# control.net
KiCad netlist of a schematic drawn in Altium Designer
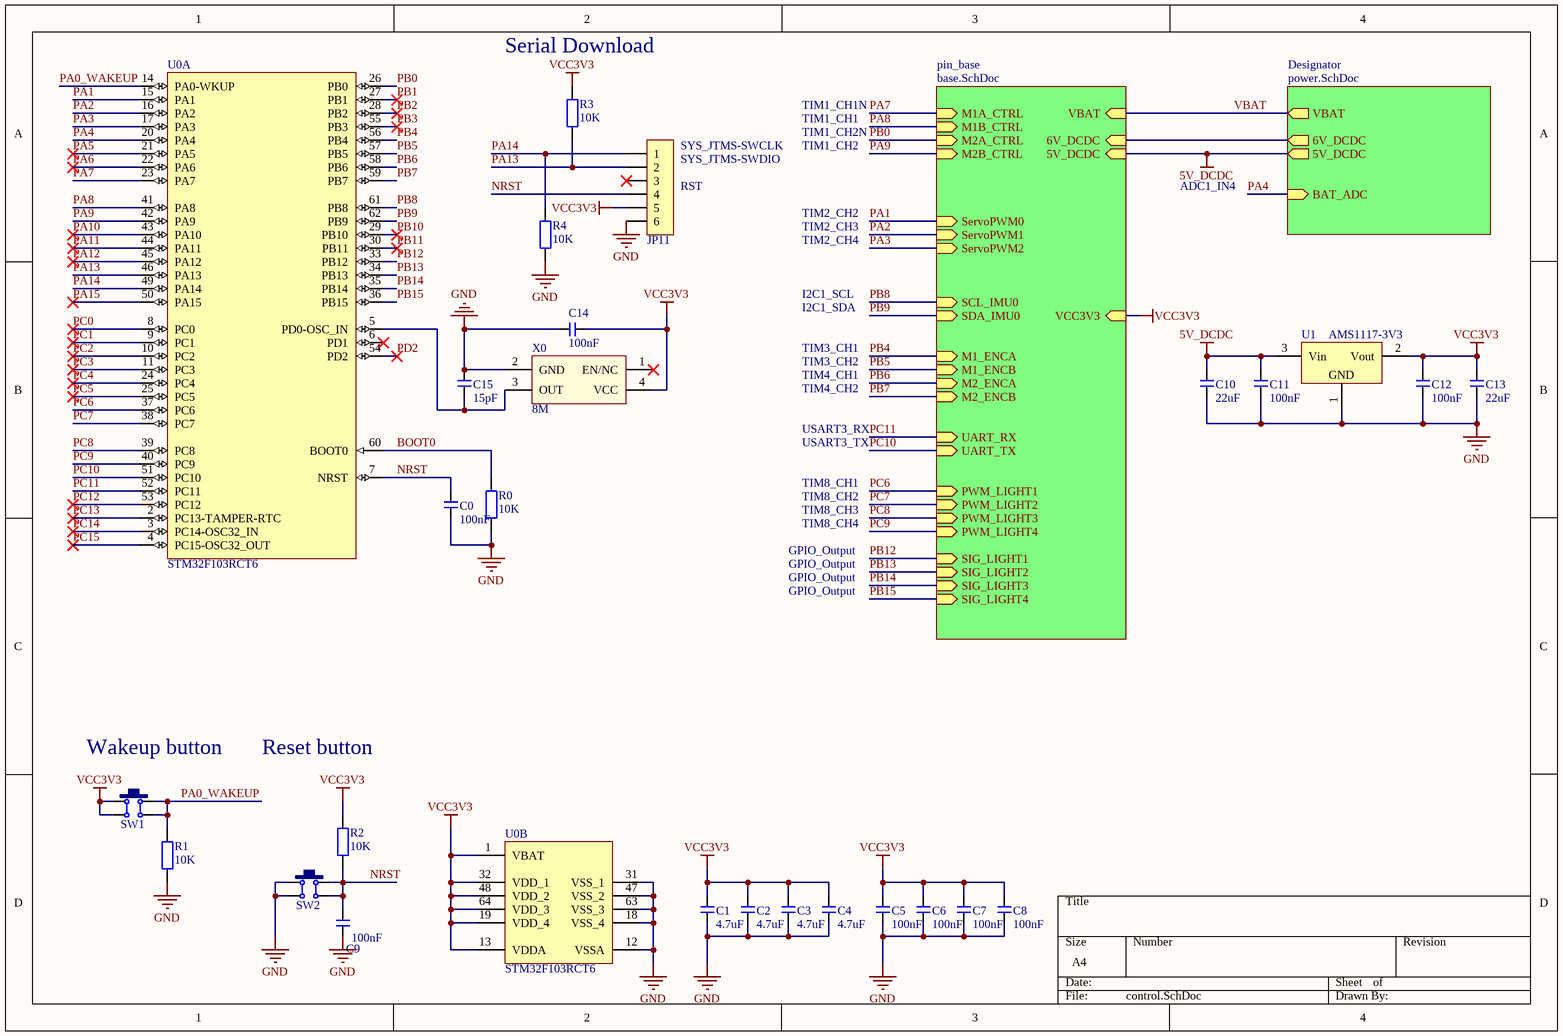
[diagram p0: control.SchDoc]

(export (version "E")
  (design (tool "Eeschema 10.0.6"))
  (components
    (comp (ref "C0")
      (value "100nF")
      (footprint "C 0402_M")
      (description "贴片电容")
      (libsource (lib "RLC") (part "C"))
    )
    (comp (ref "C1")
      (value "4.7uF")
      (footprint "C 0603_M")
      (description "贴片电容")
      (libsource (lib "RLC") (part "C"))
    )
    (comp (ref "C2")
      (value "4.7uF")
      (footprint "C 0603_M")
      (description "贴片电容")
      (libsource (lib "RLC") (part "C"))
    )
    (comp (ref "C3")
      (value "4.7uF")
      (footprint "C 0603_M")
      (description "贴片电容")
      (libsource (lib "RLC") (part "C"))
    )
    (comp (ref "C4")
      (value "4.7uF")
      (footprint "C 0603_M")
      (description "贴片电容")
      (libsource (lib "RLC") (part "C"))
    )
    (comp (ref "C5")
      (value "100nF")
      (footprint "C 0402_M")
      (description "贴片电容")
      (libsource (lib "RLC") (part "C"))
    )
    (comp (ref "C6")
      (value "100nF")
      (footprint "C 0402_M")
      (description "贴片电容")
      (libsource (lib "RLC") (part "C"))
    )
    (comp (ref "C7")
      (value "100nF")
      (footprint "C 0402_M")
      (description "贴片电容")
      (libsource (lib "RLC") (part "C"))
    )
    (comp (ref "C8")
      (value "100nF")
      (footprint "C 0402_M")
      (description "贴片电容")
      (libsource (lib "RLC") (part "C"))
    )
    (comp (ref "C9")
      (value "100nF")
      (footprint "C 0402_M")
      (description "贴片电容")
      (libsource (lib "RLC") (part "C"))
    )
    (comp (ref "C10")
      (value "22uF")
      (footprint "C 1206_M")
      (description "贴片电容")
      (libsource (lib "RLC") (part "C"))
    )
    (comp (ref "C11")
      (value "100nF")
      (footprint "C 0402_M")
      (description "贴片电容")
      (libsource (lib "RLC") (part "C"))
    )
    (comp (ref "C12")
      (value "100nF")
      (footprint "C 0402_M")
      (description "贴片电容")
      (libsource (lib "RLC") (part "C"))
    )
    (comp (ref "C13")
      (value "22uF")
      (footprint "C 1206_M")
      (description "贴片电容")
      (libsource (lib "RLC") (part "C"))
    )
    (comp (ref "C14")
      (value "100nF")
      (footprint "C 0402_M")
      (description "贴片电容")
      (libsource (lib "RLC") (part "C"))
    )
    (comp (ref "C15")
      (value "15pF")
      (footprint "C 0402_M")
      (description "贴片电容")
      (libsource (lib "RLC") (part "C"))
    )
    (comp (ref "JP11")
      (value "HDR-1X6")
      (footprint "HDR2.54-WI-6P")
      (description "6P接插件")
      (fields (field (name "版权归属") "封装库来自淘宝 ID：黄晶宝石"))
      (libsource (lib "header") (part "Header 6"))
    )
    (comp (ref "R0")
      (value "10K")
      (footprint "R 0402_M")
      (description "贴片电阻")
      (libsource (lib "RLC") (part "R"))
    )
    (comp (ref "R1")
      (value "10K")
      (footprint "R 0402_M")
      (description "贴片电阻")
      (libsource (lib "RLC") (part "R"))
    )
    (comp (ref "R2")
      (value "10K")
      (footprint "R 0402_M")
      (description "贴片电阻")
      (libsource (lib "RLC") (part "R"))
    )
    (comp (ref "R3")
      (value "10K")
      (footprint "R 0402_M")
      (description "贴片电阻")
      (libsource (lib "RLC") (part "R"))
    )
    (comp (ref "R4")
      (value "10K")
      (footprint "R 0402_M")
      (description "贴片电阻")
      (libsource (lib "RLC") (part "R"))
    )
    (comp (ref "SW1")
      (value "6x6x5")
      (footprint "TSW SMD-6*6*4.3")
      (description "贴片6x6轻触开关")
      (libsource (lib "Schlib") (part "TSW SMD-6x6"))
    )
    (comp (ref "SW2")
      (value "6x6x5")
      (footprint "TSW SMD-6*6*4.3")
      (description "贴片6x6轻触开关")
      (libsource (lib "Schlib") (part "TSW SMD-6x6"))
    )
    (comp (ref "U0")
      (value "STM32F103RCT6")
      (footprint "LQFP64_M")
      (libsource (lib "Schlib") (part "STM32F103RCT6"))
    )
    (comp (ref "U1")
      (value "AMS1117-3V3")
      (footprint "SOT223_L")
      (description "三端稳压芯片")
      (libsource (lib "Schlib") (part "AMS1117"))
    )
    (comp (ref "X0")
      (value "8M")
      (footprint "OSC 3225-4P")
      (description "4脚有源晶振")
      (libsource (lib "Schlib") (part "XTAL-ACT-4P"))
    )
  )
  (nets
    (net (code "2") (name "/BOOT0") (class "Default")
      (node (ref "R0") (pin "2") (pinfunction "2_2") (pintype "passive"))
      (node (ref "U0") (pin "60") (pinfunction "BOOT0_60") (pintype "input"))
    )
    (net (code "3") (name "/NRST") (class "Default")
      (node (ref "C0") (pin "2") (pinfunction "2_2") (pintype "passive"))
      (node (ref "C9") (pin "2") (pinfunction "2_2") (pintype "passive"))
      (node (ref "JP11") (pin "4") (pinfunction "4_4") (pintype "passive"))
      (node (ref "R2") (pin "1") (pinfunction "1_1") (pintype "passive"))
      (node (ref "SW2") (pin "2") (pinfunction "2_2") (pintype "passive"))
      (node (ref "SW2") (pin "3") (pinfunction "3_3") (pintype "passive"))
      (node (ref "U0") (pin "7") (pinfunction "NRST_7") (pintype "bidirectional"))
    )
    (net (code "4") (name "/PA0_WAKEUP") (class "Default")
      (node (ref "R1") (pin "2") (pinfunction "2_2") (pintype "passive"))
      (node (ref "SW1") (pin "2") (pinfunction "2_2") (pintype "passive"))
      (node (ref "SW1") (pin "3") (pinfunction "3_3") (pintype "passive"))
      (node (ref "U0") (pin "14") (pinfunction "PA0-WKUP_14") (pintype "bidirectional"))
    )
    (net (code "5") (name "/PA1") (class "Default")
      (node (ref "U0") (pin "15") (pinfunction "PA1_15") (pintype "bidirectional"))
    )
    (net (code "6") (name "/PA2") (class "Default")
      (node (ref "U0") (pin "16") (pinfunction "PA2_16") (pintype "bidirectional"))
    )
    (net (code "7") (name "/PA3") (class "Default")
      (node (ref "U0") (pin "17") (pinfunction "PA3_17") (pintype "bidirectional"))
    )
    (net (code "8") (name "/PA4") (class "Default")
      (node (ref "U0") (pin "20") (pinfunction "PA4_20") (pintype "bidirectional"))
    )
    (net (code "9") (name "/PA5") (class "Default")
      (node (ref "U0") (pin "21") (pinfunction "PA5_21") (pintype "bidirectional+no_connect"))
    )
    (net (code "10") (name "/PA6") (class "Default")
      (node (ref "U0") (pin "22") (pinfunction "PA6_22") (pintype "bidirectional+no_connect"))
    )
    (net (code "11") (name "/PA7") (class "Default")
      (node (ref "U0") (pin "23") (pinfunction "PA7_23") (pintype "bidirectional"))
    )
    (net (code "12") (name "/PA8") (class "Default")
      (node (ref "U0") (pin "41") (pinfunction "PA8_41") (pintype "bidirectional"))
    )
    (net (code "13") (name "/PA9") (class "Default")
      (node (ref "U0") (pin "42") (pinfunction "PA9_42") (pintype "bidirectional"))
    )
    (net (code "14") (name "/PA10") (class "Default")
      (node (ref "U0") (pin "43") (pinfunction "PA10_43") (pintype "bidirectional+no_connect"))
    )
    (net (code "15") (name "/PA11") (class "Default")
      (node (ref "U0") (pin "44") (pinfunction "PA11_44") (pintype "bidirectional+no_connect"))
    )
    (net (code "16") (name "/PA12") (class "Default")
      (node (ref "U0") (pin "45") (pinfunction "PA12_45") (pintype "bidirectional+no_connect"))
    )
    (net (code "17") (name "/PA13") (class "Default")
      (node (ref "JP11") (pin "2") (pinfunction "2_2") (pintype "passive"))
      (node (ref "R3") (pin "1") (pinfunction "1_1") (pintype "passive"))
      (node (ref "U0") (pin "46") (pinfunction "PA13_46") (pintype "bidirectional"))
    )
    (net (code "18") (name "/PA14") (class "Default")
      (node (ref "JP11") (pin "1") (pinfunction "1_1") (pintype "passive"))
      (node (ref "R4") (pin "2") (pinfunction "2_2") (pintype "passive"))
      (node (ref "U0") (pin "49") (pinfunction "PA14_49") (pintype "bidirectional"))
    )
    (net (code "19") (name "/PA15") (class "Default")
      (node (ref "U0") (pin "50") (pinfunction "PA15_50") (pintype "bidirectional+no_connect"))
    )
    (net (code "20") (name "/PB0") (class "Default")
      (node (ref "U0") (pin "26") (pinfunction "PB0_26") (pintype "bidirectional"))
    )
    (net (code "21") (name "/PB1") (class "Default")
      (node (ref "U0") (pin "27") (pinfunction "PB1_27") (pintype "bidirectional+no_connect"))
    )
    (net (code "22") (name "/PB2") (class "Default")
      (node (ref "U0") (pin "28") (pinfunction "PB2_28") (pintype "bidirectional+no_connect"))
    )
    (net (code "23") (name "/PB3") (class "Default")
      (node (ref "U0") (pin "55") (pinfunction "PB3_55") (pintype "bidirectional+no_connect"))
    )
    (net (code "24") (name "/PB4") (class "Default")
      (node (ref "U0") (pin "56") (pinfunction "PB4_56") (pintype "bidirectional"))
    )
    (net (code "25") (name "/PB5") (class "Default")
      (node (ref "U0") (pin "57") (pinfunction "PB5_57") (pintype "bidirectional"))
    )
    (net (code "26") (name "/PB6") (class "Default")
      (node (ref "U0") (pin "58") (pinfunction "PB6_58") (pintype "bidirectional"))
    )
    (net (code "27") (name "/PB7") (class "Default")
      (node (ref "U0") (pin "59") (pinfunction "PB7_59") (pintype "bidirectional"))
    )
    (net (code "28") (name "/PB8") (class "Default")
      (node (ref "U0") (pin "61") (pinfunction "PB8_61") (pintype "bidirectional"))
    )
    (net (code "29") (name "/PB9") (class "Default")
      (node (ref "U0") (pin "62") (pinfunction "PB9_62") (pintype "bidirectional"))
    )
    (net (code "30") (name "/PB10") (class "Default")
      (node (ref "U0") (pin "29") (pinfunction "PB10_29") (pintype "bidirectional+no_connect"))
    )
    (net (code "31") (name "/PB11") (class "Default")
      (node (ref "U0") (pin "30") (pinfunction "PB11_30") (pintype "bidirectional+no_connect"))
    )
    (net (code "32") (name "/PB12") (class "Default")
      (node (ref "U0") (pin "33") (pinfunction "PB12_33") (pintype "bidirectional"))
    )
    (net (code "33") (name "/PB13") (class "Default")
      (node (ref "U0") (pin "34") (pinfunction "PB13_34") (pintype "bidirectional"))
    )
    (net (code "34") (name "/PB14") (class "Default")
      (node (ref "U0") (pin "35") (pinfunction "PB14_35") (pintype "bidirectional"))
    )
    (net (code "35") (name "/PB15") (class "Default")
      (node (ref "U0") (pin "36") (pinfunction "PB15_36") (pintype "bidirectional"))
    )
    (net (code "36") (name "/PC0") (class "Default")
      (node (ref "U0") (pin "8") (pinfunction "PC0_8") (pintype "bidirectional+no_connect"))
    )
    (net (code "37") (name "/PC1") (class "Default")
      (node (ref "U0") (pin "9") (pinfunction "PC1_9") (pintype "bidirectional+no_connect"))
    )
    (net (code "38") (name "/PC2") (class "Default")
      (node (ref "U0") (pin "10") (pinfunction "PC2_10") (pintype "bidirectional+no_connect"))
    )
    (net (code "39") (name "/PC3") (class "Default")
      (node (ref "U0") (pin "11") (pinfunction "PC3_11") (pintype "bidirectional+no_connect"))
    )
    (net (code "40") (name "/PC4") (class "Default")
      (node (ref "U0") (pin "24") (pinfunction "PC4_24") (pintype "bidirectional+no_connect"))
    )
    (net (code "41") (name "/PC5") (class "Default")
      (node (ref "U0") (pin "25") (pinfunction "PC5_25") (pintype "bidirectional+no_connect"))
    )
    (net (code "42") (name "/PC6") (class "Default")
      (node (ref "U0") (pin "37") (pinfunction "PC6_37") (pintype "bidirectional"))
    )
    (net (code "43") (name "/PC7") (class "Default")
      (node (ref "U0") (pin "38") (pinfunction "PC7_38") (pintype "bidirectional"))
    )
    (net (code "44") (name "/PC8") (class "Default")
      (node (ref "U0") (pin "39") (pinfunction "PC8_39") (pintype "bidirectional"))
    )
    (net (code "45") (name "/PC9") (class "Default")
      (node (ref "U0") (pin "40") (pinfunction "PC9_40") (pintype "bidirectional"))
    )
    (net (code "46") (name "/PC10") (class "Default")
      (node (ref "U0") (pin "51") (pinfunction "PC10_51") (pintype "bidirectional"))
    )
    (net (code "47") (name "/PC11") (class "Default")
      (node (ref "U0") (pin "52") (pinfunction "PC11_52") (pintype "bidirectional"))
    )
    (net (code "48") (name "/PC12") (class "Default")
      (node (ref "U0") (pin "53") (pinfunction "PC12_53") (pintype "bidirectional+no_connect"))
    )
    (net (code "49") (name "/PC13") (class "Default")
      (node (ref "U0") (pin "2") (pinfunction "PC13-TAMPER-RTC_2") (pintype "bidirectional+no_connect"))
    )
    (net (code "50") (name "/PC14") (class "Default")
      (node (ref "U0") (pin "3") (pinfunction "PC14-OSC32_IN_3") (pintype "bidirectional+no_connect"))
    )
    (net (code "51") (name "/PC15") (class "Default")
      (node (ref "U0") (pin "4") (pinfunction "PC15-OSC32_OUT_4") (pintype "bidirectional+no_connect"))
    )
    (net (code "52") (name "/PD2") (class "Default")
      (node (ref "U0") (pin "54") (pinfunction "PD2_54") (pintype "bidirectional+no_connect"))
    )
    (net (code "54") (name "5V_DCDC") (class "Default")
      (node (ref "C10") (pin "2") (pinfunction "2_2") (pintype "passive"))
      (node (ref "C11") (pin "2") (pinfunction "2_2") (pintype "passive"))
      (node (ref "U1") (pin "3") (pinfunction "Vin_3") (pintype "passive"))
    )
    (net (code "55") (name "GND") (class "Default")
      (node (ref "C0") (pin "1") (pinfunction "1_1") (pintype "passive"))
      (node (ref "C1") (pin "1") (pinfunction "1_1") (pintype "passive"))
      (node (ref "C10") (pin "1") (pinfunction "1_1") (pintype "passive"))
      (node (ref "C11") (pin "1") (pinfunction "1_1") (pintype "passive"))
      (node (ref "C12") (pin "1") (pinfunction "1_1") (pintype "passive"))
      (node (ref "C13") (pin "1") (pinfunction "1_1") (pintype "passive"))
      (node (ref "C14") (pin "2") (pinfunction "2_2") (pintype "passive"))
      (node (ref "C15") (pin "1") (pinfunction "1_1") (pintype "passive"))
      (node (ref "C2") (pin "1") (pinfunction "1_1") (pintype "passive"))
      (node (ref "C3") (pin "1") (pinfunction "1_1") (pintype "passive"))
      (node (ref "C4") (pin "1") (pinfunction "1_1") (pintype "passive"))
      (node (ref "C5") (pin "1") (pinfunction "1_1") (pintype "passive"))
      (node (ref "C6") (pin "1") (pinfunction "1_1") (pintype "passive"))
      (node (ref "C7") (pin "1") (pinfunction "1_1") (pintype "passive"))
      (node (ref "C8") (pin "1") (pinfunction "1_1") (pintype "passive"))
      (node (ref "C9") (pin "1") (pinfunction "1_1") (pintype "passive"))
      (node (ref "JP11") (pin "6") (pinfunction "6_6") (pintype "passive"))
      (node (ref "R0") (pin "1") (pinfunction "1_1") (pintype "passive"))
      (node (ref "R1") (pin "1") (pinfunction "1_1") (pintype "passive"))
      (node (ref "R4") (pin "1") (pinfunction "1_1") (pintype "passive"))
      (node (ref "SW2") (pin "1") (pinfunction "1_1") (pintype "passive"))
      (node (ref "SW2") (pin "4") (pinfunction "4_4") (pintype "passive"))
      (node (ref "U0") (pin "12") (pinfunction "VSSA_12") (pintype "power_in"))
      (node (ref "U0") (pin "18") (pinfunction "VSS_4_18") (pintype "power_in"))
      (node (ref "U0") (pin "31") (pinfunction "VSS_1_31") (pintype "power_in"))
      (node (ref "U0") (pin "47") (pinfunction "VSS_2_47") (pintype "power_in"))
      (node (ref "U0") (pin "63") (pinfunction "VSS_3_63") (pintype "power_in"))
      (node (ref "U1") (pin "1") (pinfunction "GND_1") (pintype "passive"))
      (node (ref "X0") (pin "2") (pinfunction "GND_2") (pintype "passive"))
    )
    (net (code "56") (name "Net-(U0A-PD0-OSC_IN)") (class "Default")
      (node (ref "C15") (pin "2") (pinfunction "2_2") (pintype "passive"))
      (node (ref "U0") (pin "5") (pinfunction "PD0-OSC_IN_5") (pintype "bidirectional"))
      (node (ref "X0") (pin "3") (pinfunction "OUT_3") (pintype "passive"))
    )
    (net (code "57") (name "VCC3V3") (class "Default")
      (node (ref "C1") (pin "2") (pinfunction "2_2") (pintype "passive"))
      (node (ref "C12") (pin "2") (pinfunction "2_2") (pintype "passive"))
      (node (ref "C13") (pin "2") (pinfunction "2_2") (pintype "passive"))
      (node (ref "C14") (pin "1") (pinfunction "1_1") (pintype "passive"))
      (node (ref "C2") (pin "2") (pinfunction "2_2") (pintype "passive"))
      (node (ref "C3") (pin "2") (pinfunction "2_2") (pintype "passive"))
      (node (ref "C4") (pin "2") (pinfunction "2_2") (pintype "passive"))
      (node (ref "C5") (pin "2") (pinfunction "2_2") (pintype "passive"))
      (node (ref "C6") (pin "2") (pinfunction "2_2") (pintype "passive"))
      (node (ref "C7") (pin "2") (pinfunction "2_2") (pintype "passive"))
      (node (ref "C8") (pin "2") (pinfunction "2_2") (pintype "passive"))
      (node (ref "JP11") (pin "5") (pinfunction "5_5") (pintype "passive"))
      (node (ref "R2") (pin "2") (pinfunction "2_2") (pintype "passive"))
      (node (ref "R3") (pin "2") (pinfunction "2_2") (pintype "passive"))
      (node (ref "SW1") (pin "1") (pinfunction "1_1") (pintype "passive"))
      (node (ref "SW1") (pin "4") (pinfunction "4_4") (pintype "passive"))
      (node (ref "U0") (pin "1") (pinfunction "VBAT_1") (pintype "power_in"))
      (node (ref "U0") (pin "13") (pinfunction "VDDA_13") (pintype "power_in"))
      (node (ref "U0") (pin "19") (pinfunction "VDD_4_19") (pintype "power_in"))
      (node (ref "U0") (pin "32") (pinfunction "VDD_1_32") (pintype "power_in"))
      (node (ref "U0") (pin "48") (pinfunction "VDD_2_48") (pintype "power_in"))
      (node (ref "U0") (pin "64") (pinfunction "VDD_3_64") (pintype "power_in"))
      (node (ref "U1") (pin "2") (pinfunction "Vout_2") (pintype "passive"))
      (node (ref "X0") (pin "4") (pinfunction "VCC_4") (pintype "passive"))
    )
    (net (code "58") (name "unconnected-(JP11-Pad3)") (class "Default")
      (node (ref "JP11") (pin "3") (pinfunction "3_3") (pintype "passive+no_connect"))
    )
    (net (code "59") (name "unconnected-(U0A-PD1-Pad6)") (class "Default")
      (node (ref "U0") (pin "6") (pinfunction "PD1_6") (pintype "bidirectional+no_connect"))
    )
    (net (code "60") (name "unconnected-(X0-EN{slash}NC-Pad1)") (class "Default")
      (node (ref "X0") (pin "1") (pinfunction "EN/NC_1") (pintype "passive+no_connect"))
    )
  )
)
